# Power.net
KiCad netlist of a schematic drawn in Altium Designer
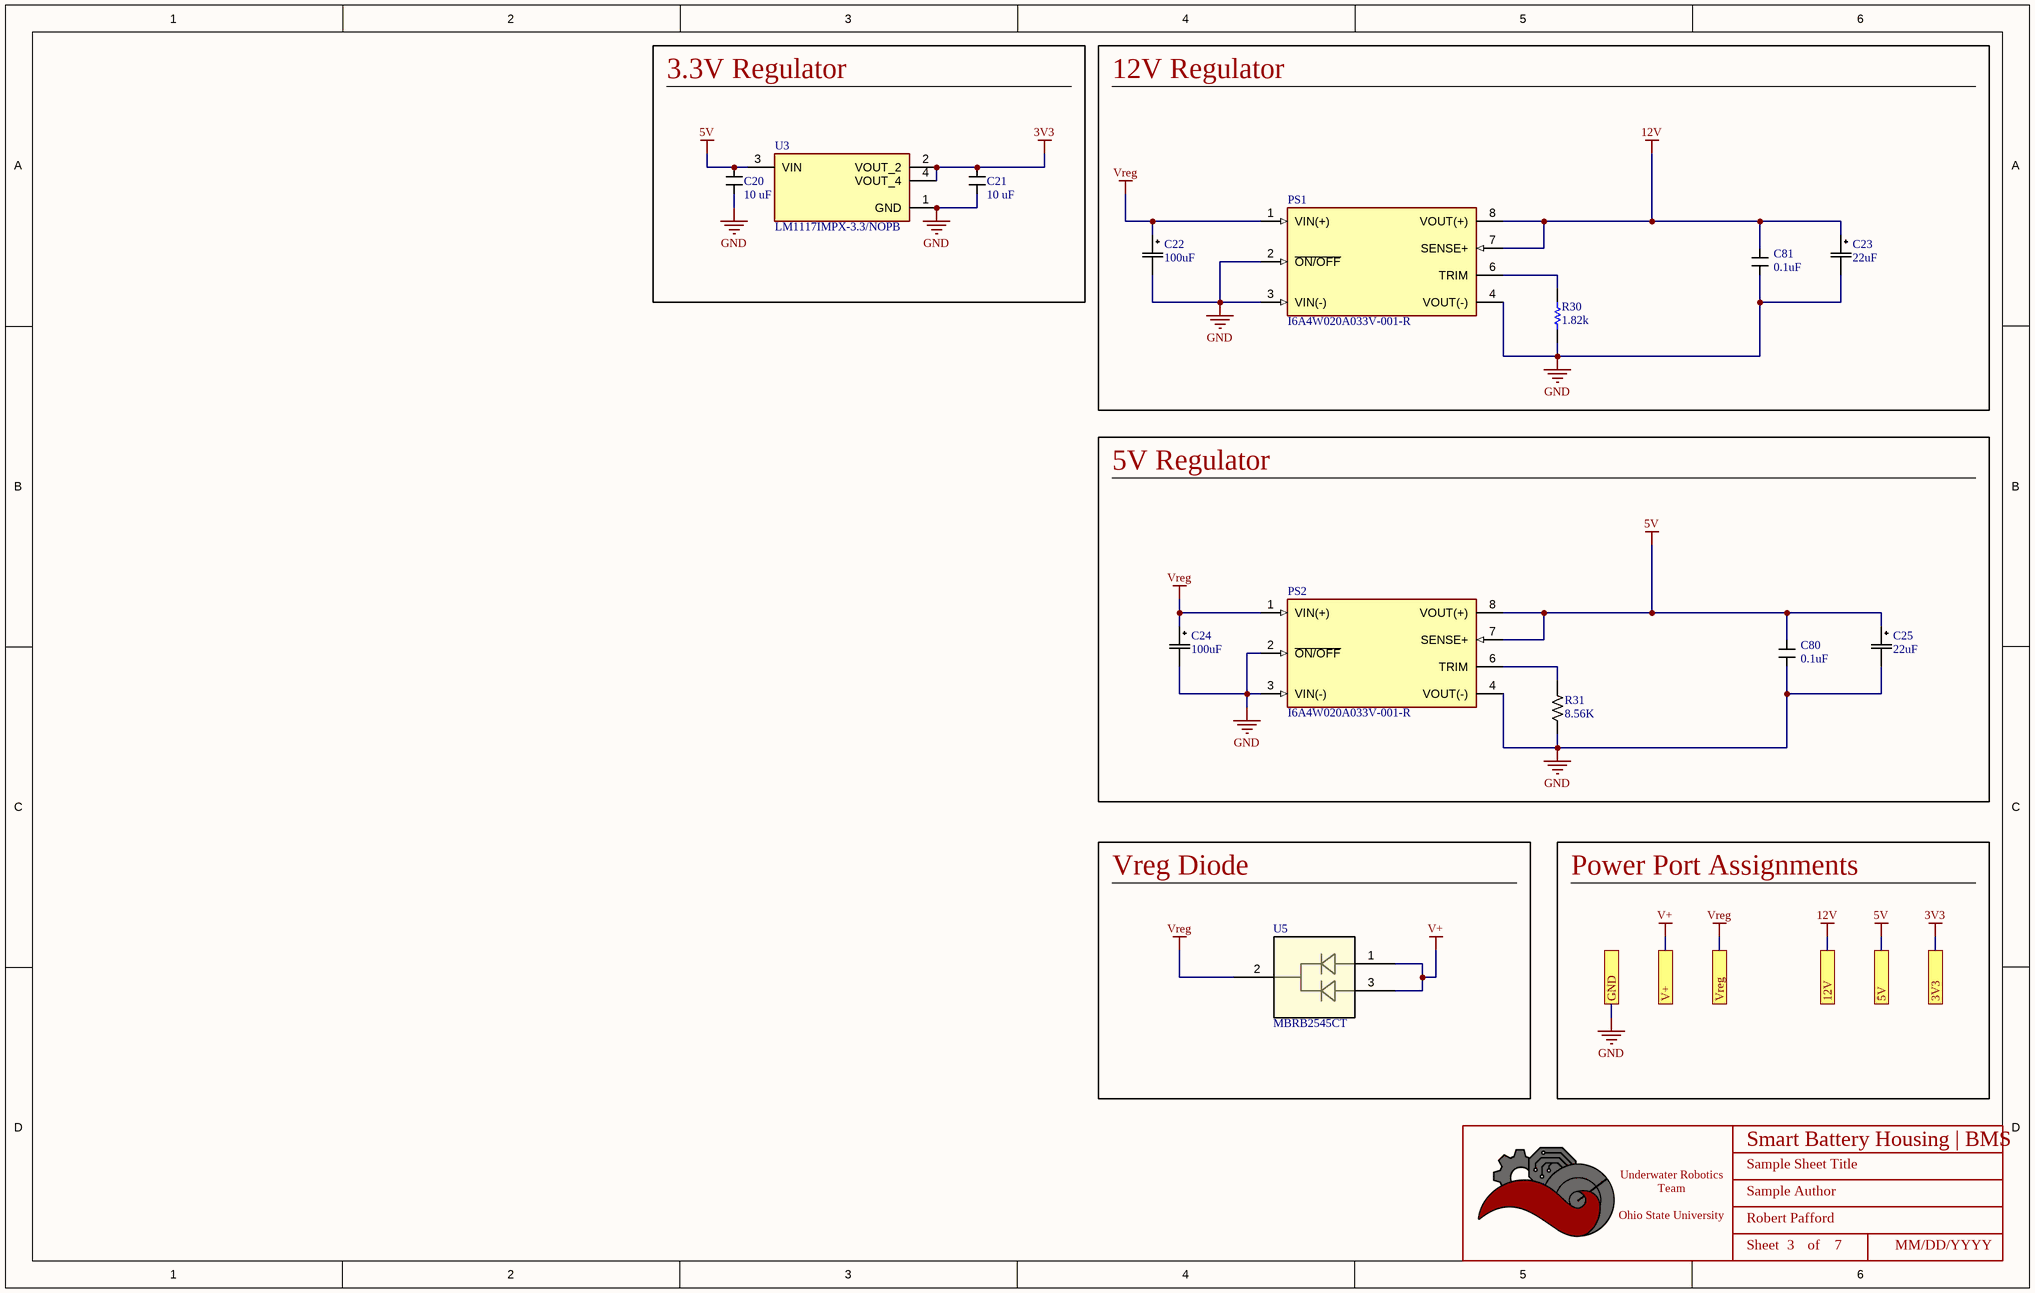
[diagram p0: Power.SchDoc]

(export (version "E")
  (design (tool "Eeschema 10.0.6"))
  (components
    (comp (ref "C20")
      (value "10uF Ceramic 6.3V")
      (footprint "CAPACITOR_0603")
      (description "Cap 10uF 6.3V +/-20%\r\nCeramic 0603")
      (fields
        (field (name "TOLERANCE") "+/- 20%")
        (field (name "VOLTAGE") "6.3V")
        (field (name "VALUE (UF)") "10 uF")
        (field (name "MADE BY") "Flip B")
      )
      (libsource (lib "Capacitors") (part "CAPACITOR_10uF_0603"))
    )
    (comp (ref "C21")
      (value "10uF Ceramic 6.3V")
      (footprint "CAPACITOR_0603")
      (description "Cap 10uF 6.3V +/-20%\r\nCeramic 0603")
      (fields
        (field (name "TOLERANCE") "+/- 20%")
        (field (name "VOLTAGE") "6.3V")
        (field (name "VALUE (UF)") "10 uF")
        (field (name "MADE BY") "Flip B")
      )
      (libsource (lib "Capacitors") (part "CAPACITOR_10uF_0603"))
    )
    (comp (ref "C22")
      (value "100uF")
      (footprint "PCAP_8x5.4-ELECT_NCA")
      (description "100 µF 35 V Aluminum Electrolytic Capacitors Radial, Can - SMD 1000 Hrs")
      (fields
        (field (name "MANUFACTURER_PART_NUMBER") "UCB1V0R1MCL1GS")
        (field (name "Comment") "100uF electrolytic 35 V")
        (field (name "COPYRIGHT") "Copyright (C) 2022 Ultra Librarian. All rights reserved.")
        (field (name "MADE BY") "Tyson Nguyen")
      )
      (libsource (lib "Capacitors") (part "CAP ALUM 100UF 20% 35V SMD"))
    )
    (comp (ref "C23")
      (value "22uF")
      (footprint "PCAP_8x5.4-ELECT_NCA")
      (description "22 µF 35 V Aluminum Electrolytic Capacitors Radial, Can - SMD 1000 Hrs")
      (fields
        (field (name "VOLTAGE") "35V")
        (field (name "Comment") "22uF electrolytic 35 V")
        (field (name "MADE BY") "Robert Pafford")
      )
      (libsource (lib "Capacitors") (part "CAP ALUM 22UF 20% 35V SMD"))
    )
    (comp (ref "C24")
      (value "100uF")
      (footprint "PCAP_8x5.4-ELECT_NCA")
      (description "100 µF 35 V Aluminum Electrolytic Capacitors Radial, Can - SMD 1000 Hrs")
      (fields
        (field (name "MANUFACTURER_PART_NUMBER") "UCB1V0R1MCL1GS")
        (field (name "Comment") "100uF electrolytic 35 V")
        (field (name "COPYRIGHT") "Copyright (C) 2022 Ultra Librarian. All rights reserved.")
        (field (name "MADE BY") "Tyson Nguyen")
      )
      (libsource (lib "Capacitors") (part "CAP ALUM 100UF 20% 35V SMD"))
    )
    (comp (ref "C25")
      (value "22uF")
      (footprint "PCAP_8x5.4-ELECT_NCA")
      (description "22 µF 35 V Aluminum Electrolytic Capacitors Radial, Can - SMD 1000 Hrs")
      (fields
        (field (name "VOLTAGE") "35V")
        (field (name "Comment") "22uF electrolytic 35 V")
        (field (name "MADE BY") "Robert Pafford")
      )
      (libsource (lib "Capacitors") (part "CAP ALUM 22UF 20% 35V SMD"))
    )
    (comp (ref "C80")
      (value "CL05A104KA5NNNC")
      (footprint "CAPACITOR_0402")
      (description "0.1 µF ±10% 25V Ceramic Capacitor X5R 0402 (1005 Metric)")
      (fields (field (name "CAPACITANCE") "0.1uF") (field (name "TOLERANCE") "+/- 10%"))
      (libsource (lib "Capacitors") (part "CAP CER 0.1UF 25V X5R 0402"))
    )
    (comp (ref "C81")
      (value "CL05A104KA5NNNC")
      (footprint "CAPACITOR_0402")
      (description "0.1 µF ±10% 25V Ceramic Capacitor X5R 0402 (1005 Metric)")
      (fields (field (name "CAPACITANCE") "0.1uF") (field (name "TOLERANCE") "+/- 10%"))
      (libsource (lib "Capacitors") (part "CAP CER 0.1UF 25V X5R 0402"))
    )
    (comp (ref "PS1")
      (value "I6A4W020A033V-001-R")
      (footprint "CONV_I6A4W020A033V-001-R")
      (description "Non-Isolated PoL Module DC DC Converter 1 Output 3.3 ~ 15V 20A 9V - 53V Input")
      (fields (field (name "MF") "TDK-Lambda Americas"))
      (libsource (lib "I6A4W020A033V-001-R") (part "I6A4W020A033V-001-R"))
    )
    (comp (ref "PS2")
      (value "I6A4W020A033V-001-R")
      (footprint "CONV_I6A4W020A033V-001-R")
      (description "Non-Isolated PoL Module DC DC Converter 1 Output 3.3 ~ 15V 20A 9V - 53V Input")
      (fields (field (name "MF") "TDK-Lambda Americas"))
      (libsource (lib "I6A4W020A033V-001-R") (part "I6A4W020A033V-001-R"))
    )
    (comp (ref "R30")
      (value "1.82k")
      (footprint "RESC1608X55X25ML10T15")
      (description "RC0603FR-071K82L")
      (fields (field (name "MANUFACTURER") "Yageo"))
      (libsource (lib "Altium Content Vault") (part "RES"))
    )
    (comp (ref "R31")
      (value "RES 8.56K OHM 1% 1/16W 0402")
      (footprint "RESISTOR_0402")
      (fields
        (field (name "TOLERANCE") "+/- 1%")
        (field (name "VALUE (OHMS)") "8.56K")
        (field (name "MADE BY") "John Ulm")
        (field (name "VERIFIED BY") "*")
      )
      (libsource (lib "Resistors") (part "RESISTOR_8.56K_1%_0402"))
    )
    (comp (ref "U3")
      (value "LM1117IMPX-3.3/NOPB")
      (footprint "SOT-223-4")
      (description "800-mA 15-V linear voltage regulator 4-SOT-223 -40 to 125")
      (fields (field (name "MF") "Texas Instruments"))
      (libsource (lib "Integrated Circuits") (part "LM1117IMPX-3.3/NOPB"))
    )
    (comp (ref "U5")
      (value "MBRB2545CT")
      (footprint "D2PAK_VIS")
      (description "Diode Array 1 Pair Common Cathode 45 V Surface Mount TO-263-3, D²Pak (2 Leads + Tab), TO-263AB")
      (fields (field (name "COPYRIGHT") "Copyright (C) 2023 Ultra Librarian. All rights reserved."))
      (libsource (lib "Diodes") (part "MBRB2545CT"))
    )
  )
  (nets
    (net (code "1") (name "3V3") (class "Default")
      (node (ref "C21") (pin "1") (pinfunction "1_1") (pintype "passive"))
      (node (ref "U3") (pin "2") (pinfunction "VOUT_2_2") (pintype "power_in"))
      (node (ref "U3") (pin "4") (pinfunction "VOUT_4_4") (pintype "power_in"))
    )
    (net (code "2") (name "5V") (class "Default")
      (node (ref "C20") (pin "1") (pinfunction "1_1") (pintype "passive"))
      (node (ref "C25") (pin "1") (pinfunction "1_1") (pintype "passive"))
      (node (ref "C80") (pin "1") (pinfunction "1_1") (pintype "passive"))
      (node (ref "PS2") (pin "7") (pinfunction "SENSE+_7") (pintype "input"))
      (node (ref "PS2") (pin "8") (pinfunction "VOUT(+)_8") (pintype "power_in"))
      (node (ref "U3") (pin "3") (pinfunction "VIN_3") (pintype "power_in"))
    )
    (net (code "3") (name "12V") (class "Default")
      (node (ref "C23") (pin "1") (pinfunction "1_1") (pintype "passive"))
      (node (ref "C81") (pin "1") (pinfunction "1_1") (pintype "passive"))
      (node (ref "PS1") (pin "7") (pinfunction "SENSE+_7") (pintype "input"))
      (node (ref "PS1") (pin "8") (pinfunction "VOUT(+)_8") (pintype "power_in"))
    )
    (net (code "4") (name "GND") (class "Default")
      (node (ref "C20") (pin "2") (pinfunction "2_2") (pintype "passive"))
      (node (ref "C21") (pin "2") (pinfunction "2_2") (pintype "passive"))
      (node (ref "C22") (pin "2") (pinfunction "2_2") (pintype "passive"))
      (node (ref "C23") (pin "2") (pinfunction "2_2") (pintype "passive"))
      (node (ref "C24") (pin "2") (pinfunction "2_2") (pintype "passive"))
      (node (ref "C25") (pin "2") (pinfunction "2_2") (pintype "passive"))
      (node (ref "C80") (pin "2") (pinfunction "2_2") (pintype "passive"))
      (node (ref "C81") (pin "2") (pinfunction "2_2") (pintype "passive"))
      (node (ref "PS1") (pin "2") (pinfunction "~{ON/OFF}_2") (pintype "input"))
      (node (ref "PS1") (pin "3") (pinfunction "VIN(-)_3") (pintype "input"))
      (node (ref "PS1") (pin "4") (pinfunction "VOUT(-)_4") (pintype "power_in"))
      (node (ref "PS2") (pin "2") (pinfunction "~{ON/OFF}_2") (pintype "input"))
      (node (ref "PS2") (pin "3") (pinfunction "VIN(-)_3") (pintype "input"))
      (node (ref "PS2") (pin "4") (pinfunction "VOUT(-)_4") (pintype "power_in"))
      (node (ref "R30") (pin "1") (pinfunction "1_1") (pintype "passive"))
      (node (ref "R31") (pin "2") (pinfunction "2_2") (pintype "passive"))
      (node (ref "U3") (pin "1") (pinfunction "GND_1") (pintype "power_in"))
    )
    (net (code "5") (name "Net-(PS1-TRIM)") (class "Default")
      (node (ref "PS1") (pin "6") (pinfunction "TRIM_6") (pintype "passive"))
      (node (ref "R30") (pin "2") (pinfunction "2_2") (pintype "passive"))
    )
    (net (code "6") (name "Net-(PS2-TRIM)") (class "Default")
      (node (ref "PS2") (pin "6") (pinfunction "TRIM_6") (pintype "passive"))
      (node (ref "R31") (pin "1") (pinfunction "1_1") (pintype "passive"))
    )
    (net (code "7") (name "V+") (class "Default")
      (node (ref "U5") (pin "1") (pinfunction "1_1") (pintype "passive"))
      (node (ref "U5") (pin "3") (pinfunction "3_3") (pintype "passive"))
    )
    (net (code "8") (name "Vreg") (class "Default")
      (node (ref "C22") (pin "1") (pinfunction "1_1") (pintype "passive"))
      (node (ref "C24") (pin "1") (pinfunction "1_1") (pintype "passive"))
      (node (ref "PS1") (pin "1") (pinfunction "VIN(+)_1") (pintype "input"))
      (node (ref "PS2") (pin "1") (pinfunction "VIN(+)_1") (pintype "input"))
      (node (ref "U5") (pin "2") (pinfunction "2_2") (pintype "passive"))
    )
  )
)
